# lab6_2020-12-28_17-34-32.net
KiCad netlist of a schematic drawn in EasyEDA
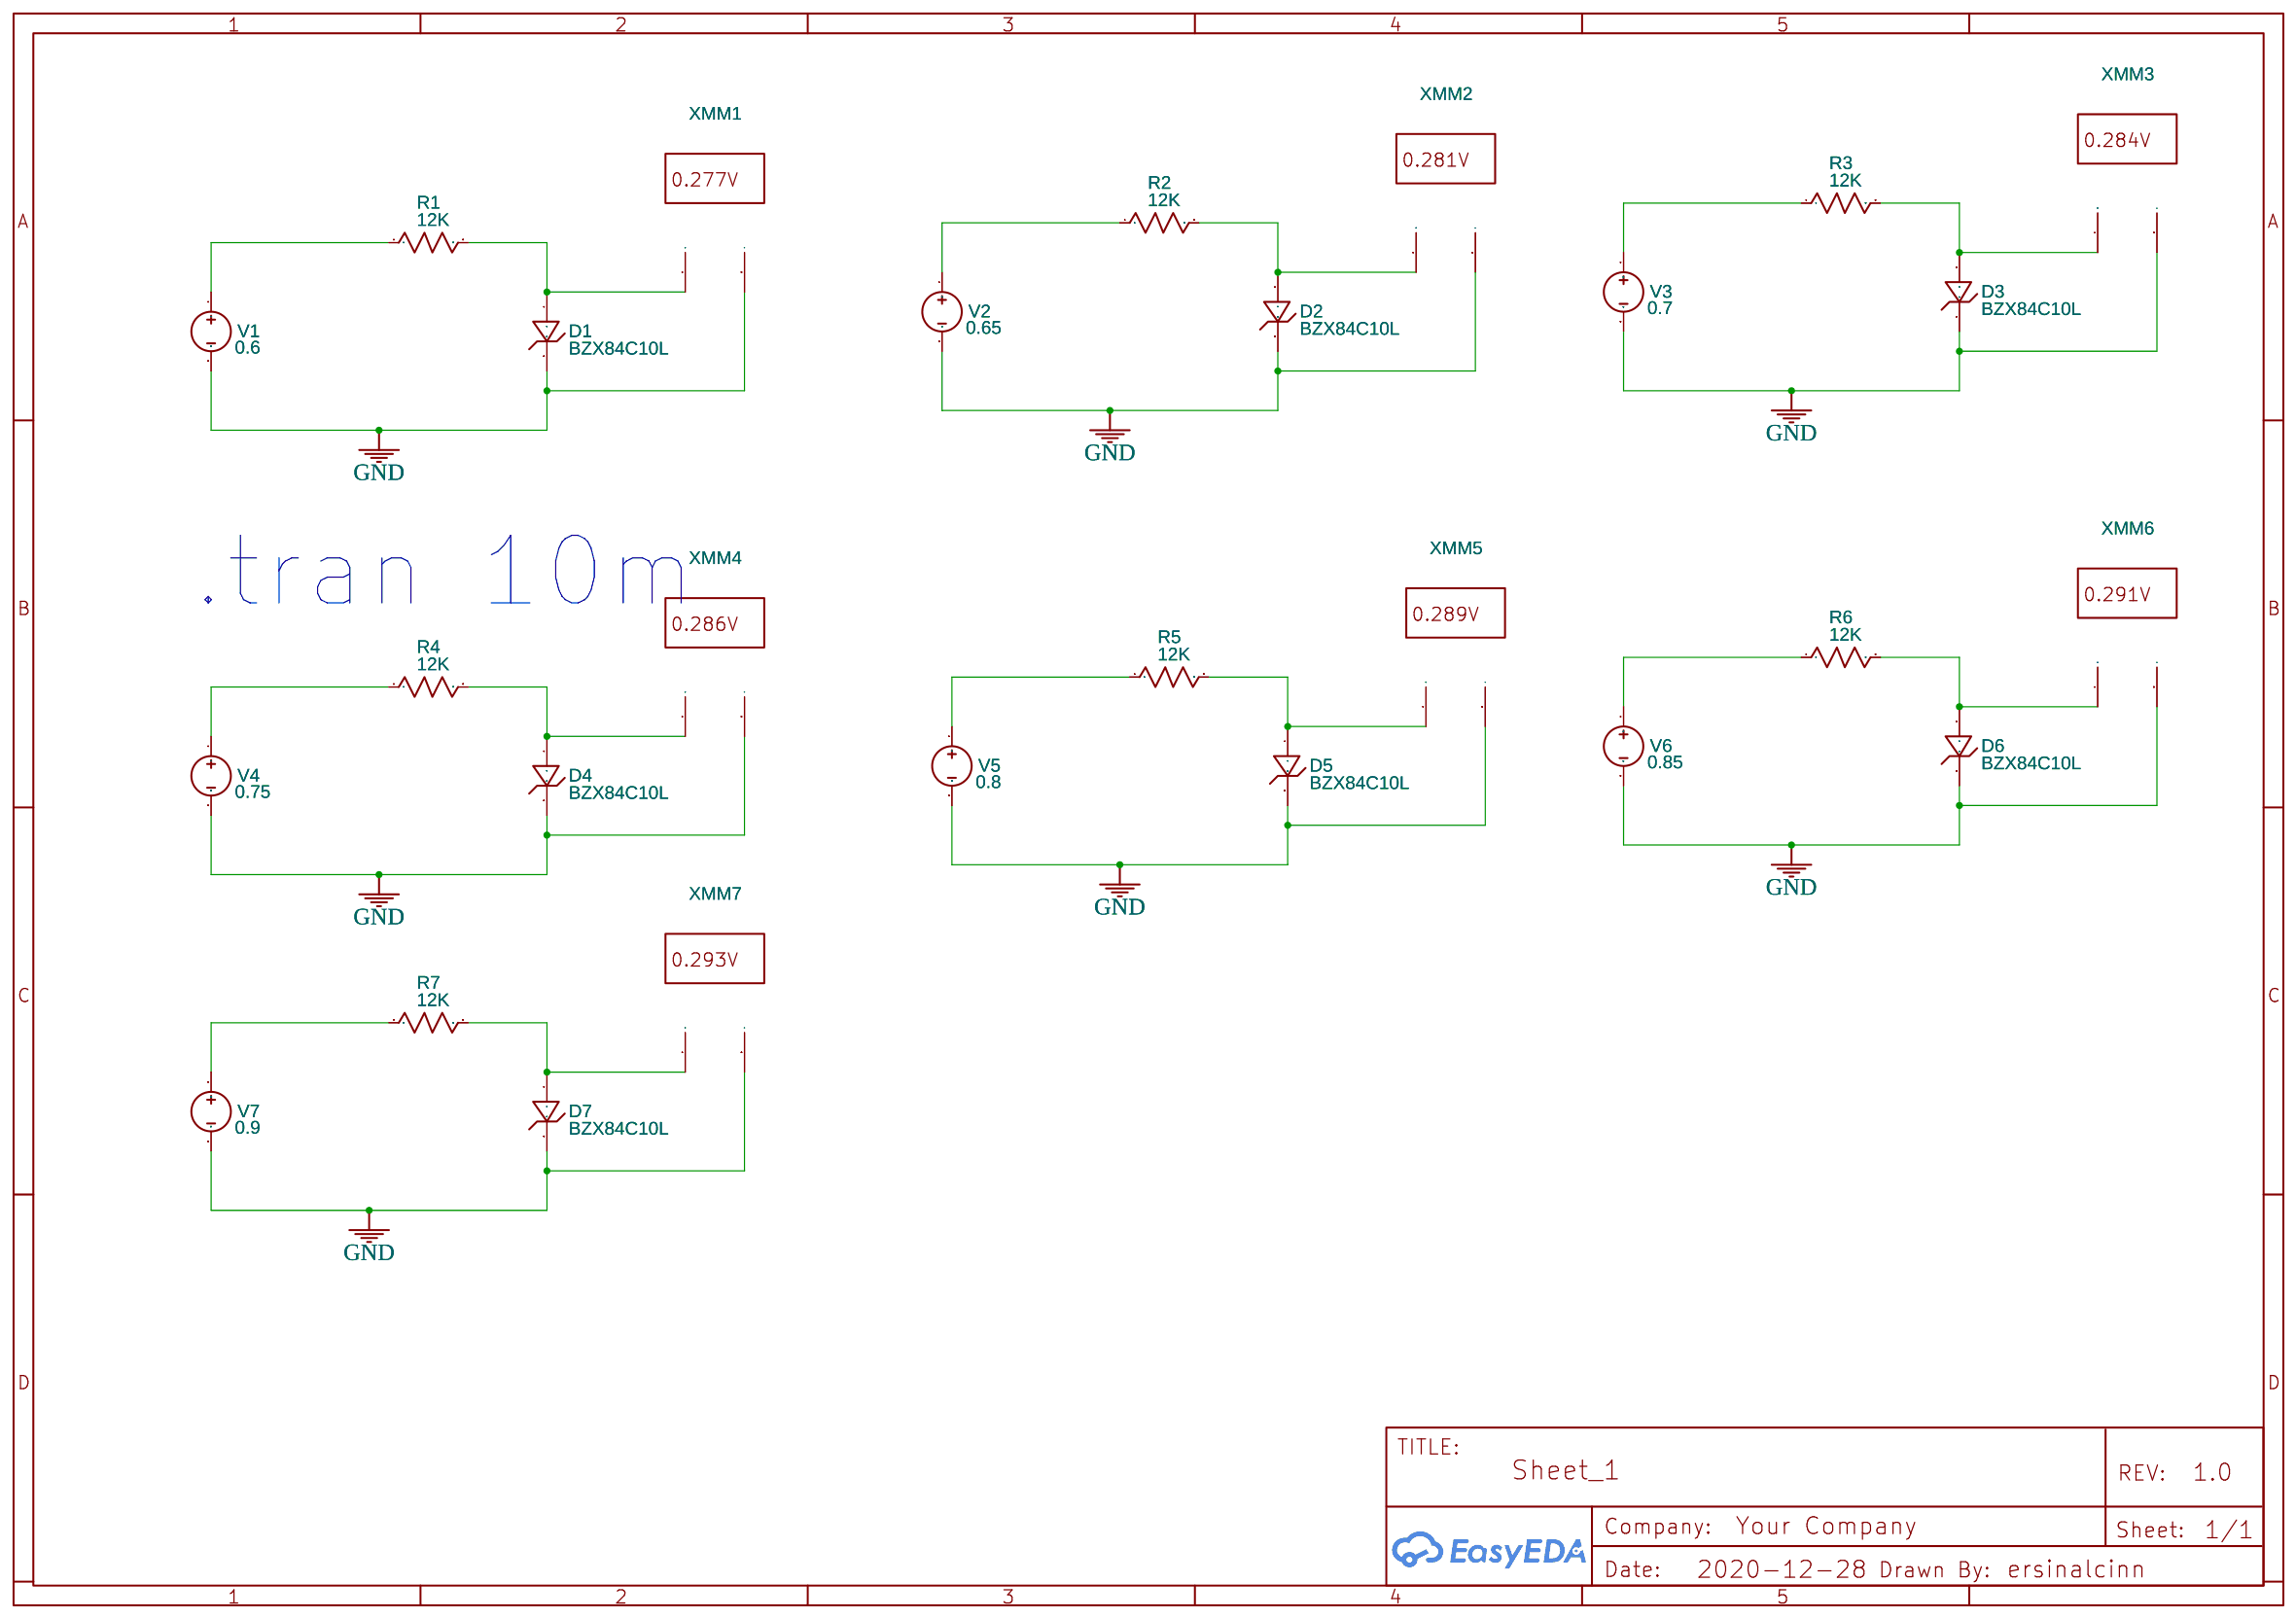
[diagram p0: schematic sheet]

(export (version "E")
  (design (tool "Eeschema 10.0.6"))
  (components
    (comp (ref "D1") (value "BZX84C10L") (libsource (lib "") (part "BZX84C10L")))
    (comp (ref "D2") (value "BZX84C10L") (libsource (lib "") (part "BZX84C10L")))
    (comp (ref "D3") (value "BZX84C10L") (libsource (lib "") (part "BZX84C10L")))
    (comp (ref "D4") (value "BZX84C10L") (libsource (lib "") (part "BZX84C10L")))
    (comp (ref "D5") (value "BZX84C10L") (libsource (lib "") (part "BZX84C10L")))
    (comp (ref "D6") (value "BZX84C10L") (libsource (lib "") (part "BZX84C10L")))
    (comp (ref "D7") (value "BZX84C10L") (libsource (lib "") (part "BZX84C10L")))
    (comp (ref "R1") (value "12K") (libsource (lib "") (part "Resistor_US")))
    (comp (ref "R2") (value "12K") (libsource (lib "") (part "Resistor_US")))
    (comp (ref "R3") (value "12K") (libsource (lib "") (part "Resistor_US")))
    (comp (ref "R4") (value "12K") (libsource (lib "") (part "Resistor_US")))
    (comp (ref "R5") (value "12K") (libsource (lib "") (part "Resistor_US")))
    (comp (ref "R6") (value "12K") (libsource (lib "") (part "Resistor_US")))
    (comp (ref "R7") (value "12K") (libsource (lib "") (part "Resistor_US")))
    (comp (ref "V1") (value "0.6") (libsource (lib "") (part "VDC")))
    (comp (ref "V2") (value "0.65") (libsource (lib "") (part "VDC")))
    (comp (ref "V3") (value "0.7") (libsource (lib "") (part "VDC")))
    (comp (ref "V4") (value "0.75") (libsource (lib "") (part "VDC")))
    (comp (ref "V5") (value "0.8") (libsource (lib "") (part "VDC")))
    (comp (ref "V6") (value "0.85") (libsource (lib "") (part "VDC")))
    (comp (ref "V7") (value "0.9") (libsource (lib "") (part "VDC")))
    (comp (ref "XMM1") (value "Multimeter") (libsource (lib "") (part "MULTIMETER_6")))
    (comp (ref "XMM2") (value "Multimeter") (libsource (lib "") (part "MULTIMETER_4")))
    (comp (ref "XMM3") (value "Multimeter") (libsource (lib "") (part "MULTIMETER_1")))
    (comp (ref "XMM4") (value "Multimeter") (libsource (lib "") (part "MULTIMETER_3")))
    (comp (ref "XMM5") (value "Multimeter") (libsource (lib "") (part "MULTIMETER_2")))
    (comp (ref "XMM6") (value "Multimeter") (libsource (lib "") (part "MULTIMETER")))
    (comp (ref "XMM7") (value "Multimeter") (libsource (lib "") (part "MULTIMETER_5")))
  )
  (nets
    (net (code "1") (name "GND") (class "Default")
      (node (ref "D1") (pin "2") (pinfunction "K_2") (pintype "unspecified"))
      (node (ref "D2") (pin "2") (pinfunction "K_2") (pintype "unspecified"))
      (node (ref "D3") (pin "2") (pinfunction "K_2") (pintype "unspecified"))
      (node (ref "D4") (pin "2") (pinfunction "K_2") (pintype "unspecified"))
      (node (ref "D5") (pin "2") (pinfunction "K_2") (pintype "unspecified"))
      (node (ref "D6") (pin "2") (pinfunction "K_2") (pintype "unspecified"))
      (node (ref "D7") (pin "2") (pinfunction "K_2") (pintype "unspecified"))
      (node (ref "V1") (pin "2") (pinfunction "2_2") (pintype "unspecified"))
      (node (ref "V2") (pin "2") (pinfunction "2_2") (pintype "unspecified"))
      (node (ref "V3") (pin "2") (pinfunction "2_2") (pintype "unspecified"))
      (node (ref "V4") (pin "2") (pinfunction "2_2") (pintype "unspecified"))
      (node (ref "V5") (pin "2") (pinfunction "2_2") (pintype "unspecified"))
      (node (ref "V6") (pin "2") (pinfunction "2_2") (pintype "unspecified"))
      (node (ref "V7") (pin "2") (pinfunction "2_2") (pintype "unspecified"))
      (node (ref "XMM1") (pin "2") (pinfunction "I_2") (pintype "unspecified"))
      (node (ref "XMM2") (pin "2") (pinfunction "I_2") (pintype "unspecified"))
      (node (ref "XMM3") (pin "2") (pinfunction "I_2") (pintype "unspecified"))
      (node (ref "XMM4") (pin "2") (pinfunction "I_2") (pintype "unspecified"))
      (node (ref "XMM5") (pin "2") (pinfunction "I_2") (pintype "unspecified"))
      (node (ref "XMM6") (pin "2") (pinfunction "I_2") (pintype "unspecified"))
      (node (ref "XMM7") (pin "2") (pinfunction "I_2") (pintype "unspecified"))
    )
    (net (code "2") (name "Net-(D1-A)") (class "Default")
      (node (ref "D1") (pin "1") (pinfunction "A_1") (pintype "unspecified"))
      (node (ref "R1") (pin "2") (pinfunction "2_2") (pintype "unspecified"))
      (node (ref "XMM1") (pin "1") (pinfunction "+_1") (pintype "unspecified"))
    )
    (net (code "3") (name "Net-(D2-A)") (class "Default")
      (node (ref "D2") (pin "1") (pinfunction "A_1") (pintype "unspecified"))
      (node (ref "R2") (pin "2") (pinfunction "2_2") (pintype "unspecified"))
      (node (ref "XMM2") (pin "1") (pinfunction "+_1") (pintype "unspecified"))
    )
    (net (code "4") (name "Net-(D3-A)") (class "Default")
      (node (ref "D3") (pin "1") (pinfunction "A_1") (pintype "unspecified"))
      (node (ref "R3") (pin "2") (pinfunction "2_2") (pintype "unspecified"))
      (node (ref "XMM3") (pin "1") (pinfunction "+_1") (pintype "unspecified"))
    )
    (net (code "5") (name "Net-(D4-A)") (class "Default")
      (node (ref "D4") (pin "1") (pinfunction "A_1") (pintype "unspecified"))
      (node (ref "R4") (pin "2") (pinfunction "2_2") (pintype "unspecified"))
      (node (ref "XMM4") (pin "1") (pinfunction "+_1") (pintype "unspecified"))
    )
    (net (code "6") (name "Net-(D5-A)") (class "Default")
      (node (ref "D5") (pin "1") (pinfunction "A_1") (pintype "unspecified"))
      (node (ref "R5") (pin "2") (pinfunction "2_2") (pintype "unspecified"))
      (node (ref "XMM5") (pin "1") (pinfunction "+_1") (pintype "unspecified"))
    )
    (net (code "7") (name "Net-(D6-A)") (class "Default")
      (node (ref "D6") (pin "1") (pinfunction "A_1") (pintype "unspecified"))
      (node (ref "R6") (pin "2") (pinfunction "2_2") (pintype "unspecified"))
      (node (ref "XMM6") (pin "1") (pinfunction "+_1") (pintype "unspecified"))
    )
    (net (code "8") (name "Net-(D7-A)") (class "Default")
      (node (ref "D7") (pin "1") (pinfunction "A_1") (pintype "unspecified"))
      (node (ref "R7") (pin "2") (pinfunction "2_2") (pintype "unspecified"))
      (node (ref "XMM7") (pin "1") (pinfunction "+_1") (pintype "unspecified"))
    )
    (net (code "9") (name "Net-(R1-Pad1)") (class "Default")
      (node (ref "R1") (pin "1") (pinfunction "1_1") (pintype "unspecified"))
      (node (ref "V1") (pin "1") (pinfunction "1_1") (pintype "unspecified"))
    )
    (net (code "10") (name "Net-(R2-Pad1)") (class "Default")
      (node (ref "R2") (pin "1") (pinfunction "1_1") (pintype "unspecified"))
      (node (ref "V2") (pin "1") (pinfunction "1_1") (pintype "unspecified"))
    )
    (net (code "11") (name "Net-(R3-Pad1)") (class "Default")
      (node (ref "R3") (pin "1") (pinfunction "1_1") (pintype "unspecified"))
      (node (ref "V3") (pin "1") (pinfunction "1_1") (pintype "unspecified"))
    )
    (net (code "12") (name "Net-(R4-Pad1)") (class "Default")
      (node (ref "R4") (pin "1") (pinfunction "1_1") (pintype "unspecified"))
      (node (ref "V4") (pin "1") (pinfunction "1_1") (pintype "unspecified"))
    )
    (net (code "13") (name "Net-(R5-Pad1)") (class "Default")
      (node (ref "R5") (pin "1") (pinfunction "1_1") (pintype "unspecified"))
      (node (ref "V5") (pin "1") (pinfunction "1_1") (pintype "unspecified"))
    )
    (net (code "14") (name "Net-(R6-Pad1)") (class "Default")
      (node (ref "R6") (pin "1") (pinfunction "1_1") (pintype "unspecified"))
      (node (ref "V6") (pin "1") (pinfunction "1_1") (pintype "unspecified"))
    )
    (net (code "15") (name "Net-(R7-Pad1)") (class "Default")
      (node (ref "R7") (pin "1") (pinfunction "1_1") (pintype "unspecified"))
      (node (ref "V7") (pin "1") (pinfunction "1_1") (pintype "unspecified"))
    )
  )
)
